# 02_Power.net
KiCad netlist of a schematic drawn in Altium Designer
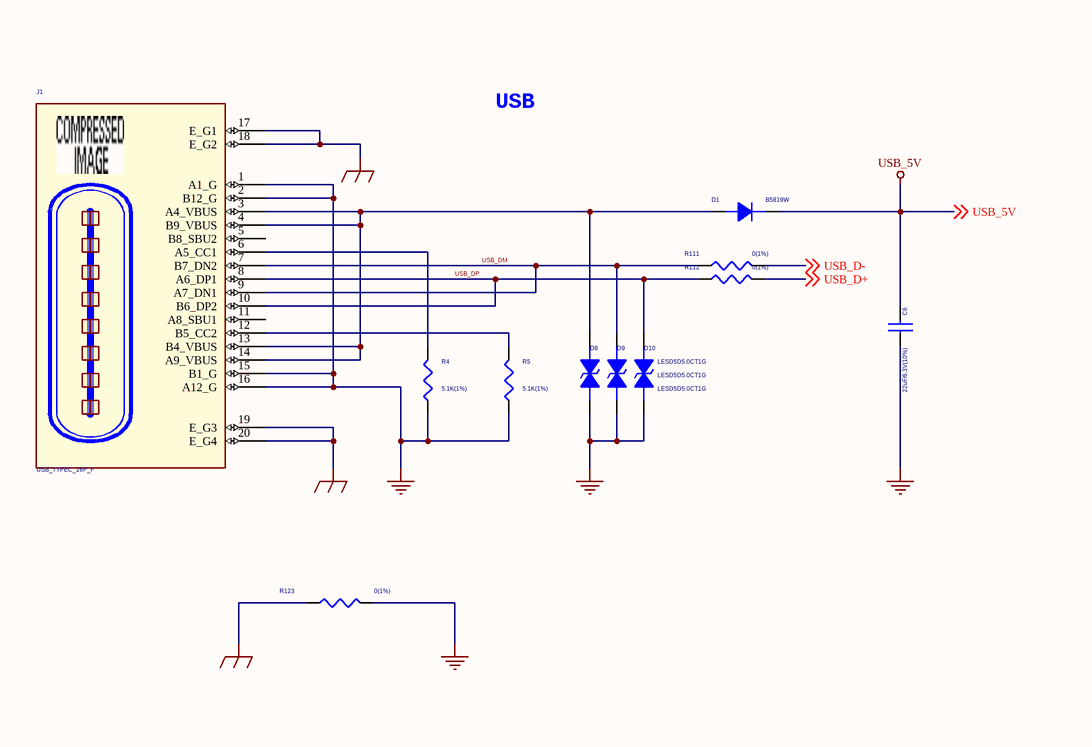
[diagram p0: 02_Power.SchDoc, left]
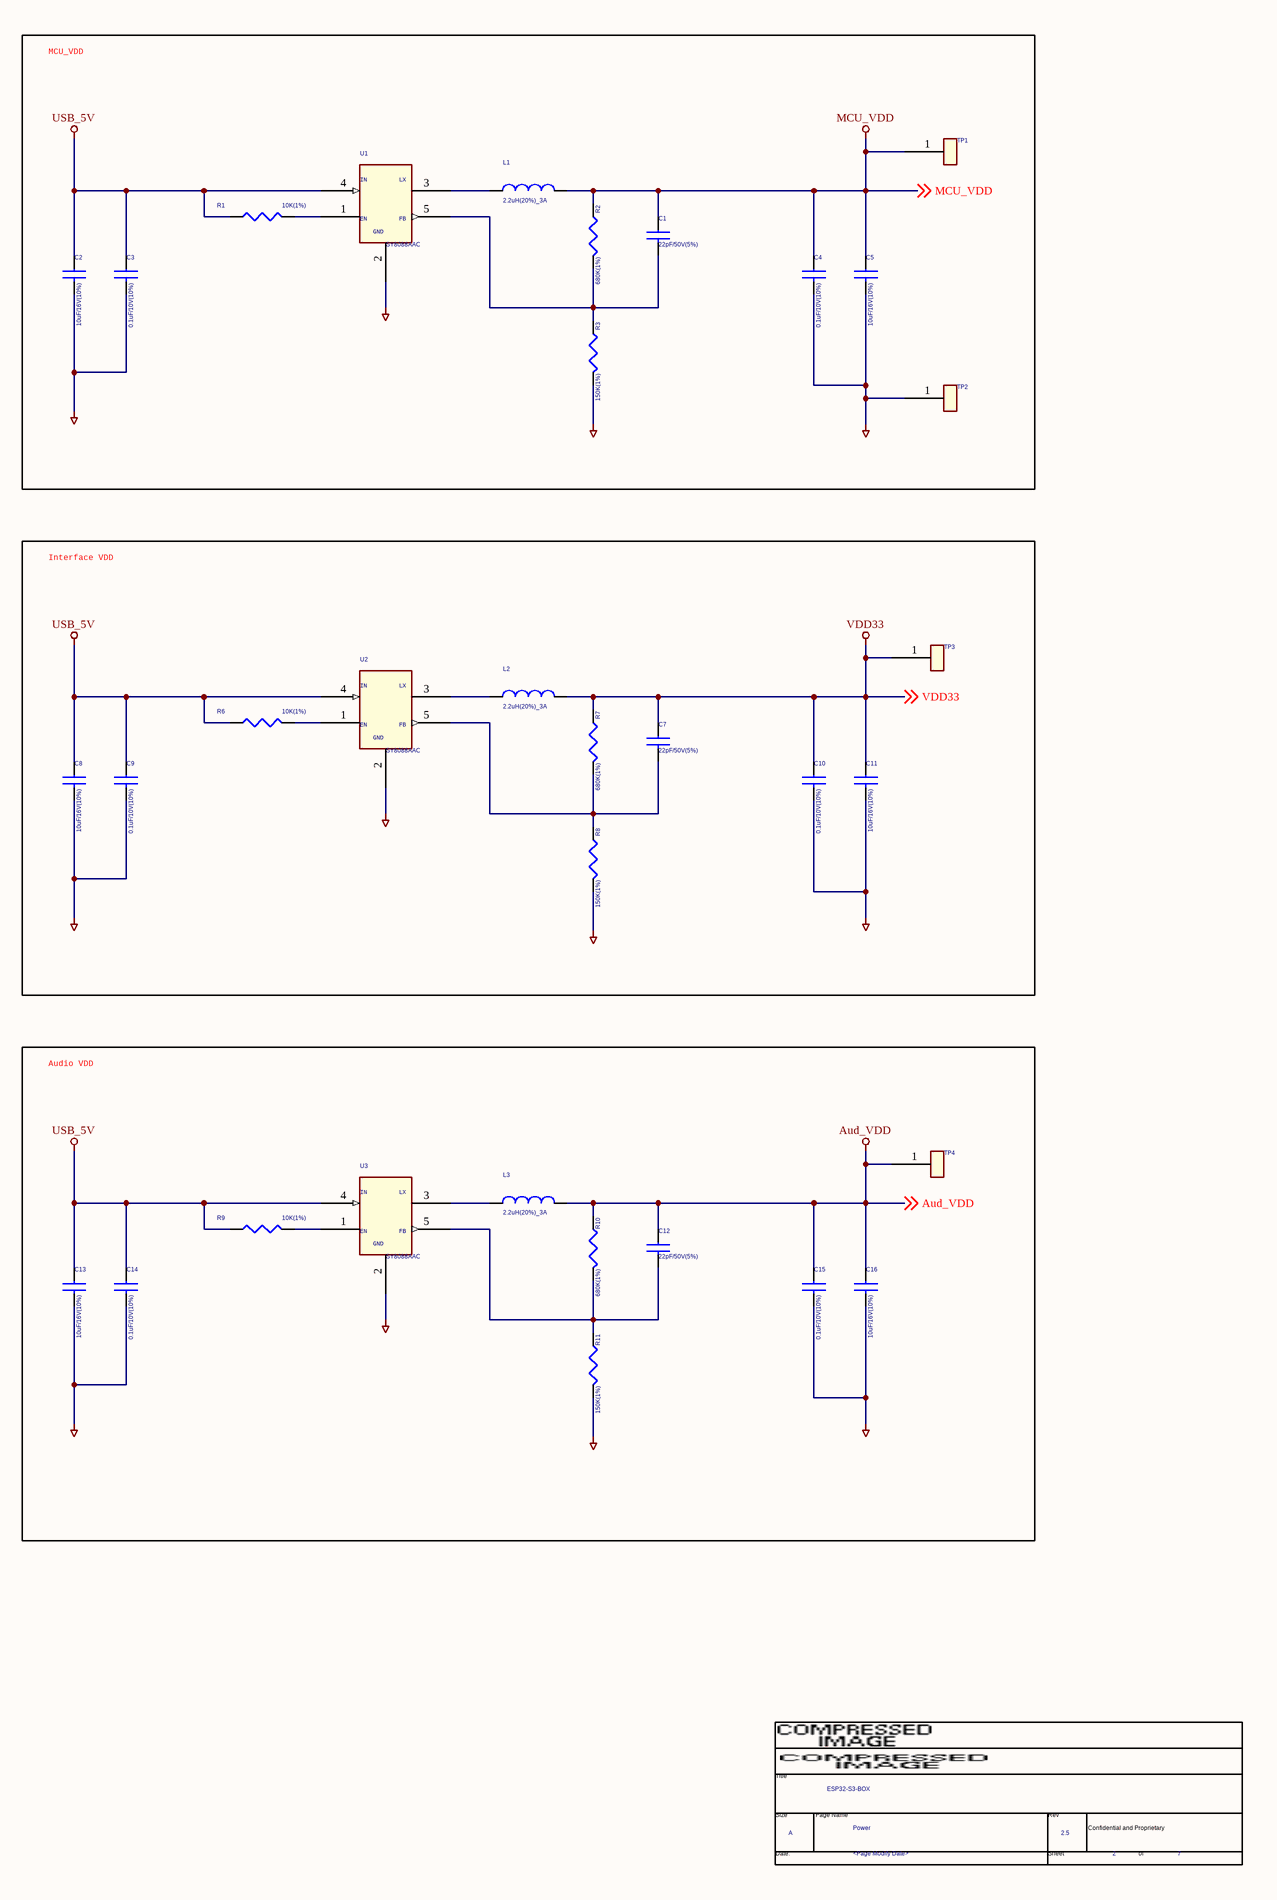
[diagram p1: 02_Power.SchDoc, right]

(export (version "E")
  (design (tool "Eeschema 10.0.6"))
  (components
    (comp (ref "*")
      (value "espTitleBlock3")
      (fields
        (field (name "PAGE MODIFY DATE") "<Page Modify Date>")
        (field (name "PAGE NAME") "Power")
        (field (name "TITLE") "ESP32-S3-BOX")
        (field (name "PAGE SIZE") "A")
        (field (name "PAGE NUMBER") "2")
        (field (name "PAGE COUNT") "7")
        (field (name "REVCODE") "2.5")
      )
      (libsource (lib "*") (part "espTitleBlock3"))
    )
    (comp (ref "C1")
      (value "22pF/50V(5%)")
      (footprint "C0402")
      (fields (field (name "PART NUMBER") "ES11041226520001"))
      (libsource (lib "*") (part "CAPACITOR"))
    )
    (comp (ref "C2")
      (value "10uF/16V(10%)")
      (footprint "C0603")
      (fields (field (name "PART NUMBER") "ES11067104600000"))
      (libsource (lib "*") (part "CAPACITOR"))
    )
    (comp (ref "C3")
      (value "0.1uF/10V(10%)")
      (footprint "C0402")
      (fields (field (name "PART NUMBER") "ES11045103620000"))
      (libsource (lib "*") (part "CAPACITOR"))
    )
    (comp (ref "C4")
      (value "0.1uF/10V(10%)")
      (footprint "C0402")
      (fields (field (name "PART NUMBER") "ES11045103620000"))
      (libsource (lib "*") (part "CAPACITOR"))
    )
    (comp (ref "C5")
      (value "10uF/16V(10%)")
      (footprint "C0603")
      (fields (field (name "PART NUMBER") "ES11067104600000"))
      (libsource (lib "*") (part "CAPACITOR"))
    )
    (comp (ref "C6")
      (value "22uF/6.3V(10%)")
      (footprint "C0603")
      (fields (field (name "PART NUMBER") "ES11067222600001"))
      (libsource (lib "*") (part "CAPACITOR"))
    )
    (comp (ref "C7")
      (value "22pF/50V(5%)")
      (footprint "C0402")
      (fields (field (name "PART NUMBER") "ES11041226520001"))
      (libsource (lib "*") (part "CAPACITOR"))
    )
    (comp (ref "C8")
      (value "10uF/16V(10%)")
      (footprint "C0603")
      (fields (field (name "PART NUMBER") "ES11067104600000"))
      (libsource (lib "*") (part "CAPACITOR"))
    )
    (comp (ref "C9")
      (value "0.1uF/10V(10%)")
      (footprint "C0402")
      (fields (field (name "PART NUMBER") "ES11045103620000"))
      (libsource (lib "*") (part "CAPACITOR"))
    )
    (comp (ref "C10")
      (value "0.1uF/10V(10%)")
      (footprint "C0402")
      (fields (field (name "PART NUMBER") "ES11045103620000"))
      (libsource (lib "*") (part "CAPACITOR"))
    )
    (comp (ref "C11")
      (value "10uF/16V(10%)")
      (footprint "C0603")
      (fields (field (name "PART NUMBER") "ES11067104600000"))
      (libsource (lib "*") (part "CAPACITOR"))
    )
    (comp (ref "C12")
      (value "22pF/50V(5%)")
      (footprint "C0402")
      (fields (field (name "PART NUMBER") "ES11041226520001"))
      (libsource (lib "*") (part "CAPACITOR"))
    )
    (comp (ref "C13")
      (value "10uF/16V(10%)")
      (footprint "C0603")
      (fields (field (name "PART NUMBER") "ES11067104600000"))
      (libsource (lib "*") (part "CAPACITOR"))
    )
    (comp (ref "C14")
      (value "0.1uF/10V(10%)")
      (footprint "C0402")
      (fields (field (name "PART NUMBER") "ES11045103620000"))
      (libsource (lib "*") (part "CAPACITOR"))
    )
    (comp (ref "C15")
      (value "0.1uF/10V(10%)")
      (footprint "C0402")
      (fields (field (name "PART NUMBER") "ES11045103620000"))
      (libsource (lib "*") (part "CAPACITOR"))
    )
    (comp (ref "C16")
      (value "10uF/16V(10%)")
      (footprint "C0603")
      (fields (field (name "PART NUMBER") "ES11067104600000"))
      (libsource (lib "*") (part "CAPACITOR"))
    )
    (comp (ref "D1")
      (value "B5819W")
      (footprint "SOD123")
      (fields (field (name "PART NUMBER") "ES31300150000000"))
      (libsource (lib "*") (part "DIODE_S"))
    )
    (comp (ref "D8")
      (value "LESD5D5.0CT1G")
      (footprint "SOD523")
      (fields (field (name "PART NUMBER") "ES31320020000000"))
      (libsource (lib "*") (part "DIODE_BI_DIR"))
    )
    (comp (ref "D9")
      (value "LESD5D5.0CT1G")
      (footprint "SOD523")
      (fields (field (name "PART NUMBER") "ES31320020000000"))
      (libsource (lib "*") (part "DIODE_BI_DIR"))
    )
    (comp (ref "D10")
      (value "LESD5D5.0CT1G")
      (footprint "SOD523")
      (fields (field (name "PART NUMBER") "ES31320020000000"))
      (libsource (lib "*") (part "DIODE_BI_DIR"))
    )
    (comp (ref "J1")
      (value "USB_TYPEC_16P_F")
      (footprint "USB_TYPEC_16P_F")
      (fields (field (name "PART NUMBER") "ES52220020000000"))
      (libsource (lib "*") (part "USB_TYPEC_16P_F"))
    )
    (comp (ref "L1")
      (value "2.2uH(20%)_3A")
      (footprint "L4040_SL")
      (libsource (lib "*") (part "INDUCTOR_Dup1"))
    )
    (comp (ref "L2")
      (value "2.2uH(20%)_3A")
      (footprint "L4040_SL")
      (libsource (lib "*") (part "INDUCTOR_Dup1"))
    )
    (comp (ref "L3")
      (value "2.2uH(20%)_3A")
      (footprint "L4040_SL")
      (libsource (lib "*") (part "INDUCTOR_Dup1"))
    )
    (comp (ref "R1")
      (value "10K(1%)")
      (footprint "R0402")
      (fields (field (name "PART NUMBER") "ES21044100000001"))
      (libsource (lib "*") (part "RESISTOR"))
    )
    (comp (ref "R2")
      (value "680K(1%)")
      (footprint "R0402")
      (fields (field (name "PART NUMBER") "ES21045680000001"))
      (libsource (lib "*") (part "RESISTOR"))
    )
    (comp (ref "R3")
      (value "150K(1%)")
      (footprint "R0402")
      (fields (field (name "PART NUMBER") "ES21045150000001"))
      (libsource (lib "*") (part "RESISTOR"))
    )
    (comp (ref "R4")
      (value "5.1K(1%)")
      (footprint "R0201")
      (fields (field (name "PART NUMBER") "ES21023510000001"))
      (libsource (lib "*") (part "RESISTOR"))
    )
    (comp (ref "R5")
      (value "5.1K(1%)")
      (footprint "R0201")
      (fields (field (name "PART NUMBER") "ES21023510000001"))
      (libsource (lib "*") (part "RESISTOR"))
    )
    (comp (ref "R6")
      (value "10K(1%)")
      (footprint "R0402")
      (fields (field (name "PART NUMBER") "ES21044100000001"))
      (libsource (lib "*") (part "RESISTOR"))
    )
    (comp (ref "R7")
      (value "680K(1%)")
      (footprint "R0402")
      (fields (field (name "PART NUMBER") "ES21045680000001"))
      (libsource (lib "*") (part "RESISTOR"))
    )
    (comp (ref "R8")
      (value "150K(1%)")
      (footprint "R0402")
      (fields (field (name "PART NUMBER") "ES21045150000001"))
      (libsource (lib "*") (part "RESISTOR"))
    )
    (comp (ref "R9")
      (value "10K(1%)")
      (footprint "R0402")
      (fields (field (name "PART NUMBER") "ES21044100000001"))
      (libsource (lib "*") (part "RESISTOR"))
    )
    (comp (ref "R10")
      (value "680K(1%)")
      (footprint "R0402")
      (fields (field (name "PART NUMBER") "ES21045680000001"))
      (libsource (lib "*") (part "RESISTOR"))
    )
    (comp (ref "R11")
      (value "150K(1%)")
      (footprint "R0402")
      (fields (field (name "PART NUMBER") "ES21045150000001"))
      (libsource (lib "*") (part "RESISTOR"))
    )
    (comp (ref "R111")
      (value "0(1%)")
      (footprint "R0201")
      (fields (field (name "PART NUMBER") "ES21020000000001"))
      (libsource (lib "*") (part "RESISTOR"))
    )
    (comp (ref "R112")
      (value "0(1%)")
      (footprint "R0201")
      (fields (field (name "PART NUMBER") "ES21020000000001"))
      (libsource (lib "*") (part "RESISTOR"))
    )
    (comp (ref "R123")
      (value "0(1%)")
      (footprint "R0603")
      (fields (field (name "PART NUMBER") "ES21060000000001"))
      (libsource (lib "*") (part "RESISTOR"))
    )
    (comp (ref "TP1") (value "TESTPOINT") (footprint "TPC_D40") (libsource (lib "*") (part "TESTPOINT")))
    (comp (ref "TP2") (value "TESTPOINT") (footprint "TPC_D40") (libsource (lib "*") (part "TESTPOINT")))
    (comp (ref "TP3") (value "TESTPOINT") (footprint "TPC_D40") (libsource (lib "*") (part "TESTPOINT")))
    (comp (ref "TP4") (value "TESTPOINT") (footprint "TPC_D40") (libsource (lib "*") (part "TESTPOINT")))
    (comp (ref "U1")
      (value "SY8088AAC")
      (footprint "SOT23-5")
      (fields (field (name "PART NUMBER") "ES41140401000000"))
      (libsource (lib "*") (part "SY808X"))
    )
    (comp (ref "U2")
      (value "SY8088AAC")
      (footprint "SOT23-5")
      (fields (field (name "PART NUMBER") "ES41140401000000"))
      (libsource (lib "*") (part "SY808X"))
    )
    (comp (ref "U3")
      (value "SY8088AAC")
      (footprint "SOT23-5")
      (fields (field (name "PART NUMBER") "ES41140401000000"))
      (libsource (lib "*") (part "SY808X"))
    )
  )
  (nets
    (net (code "1") (name "/USB_DM") (class "Default")
      (node (ref "D9") (pin "2") (pinfunction "2_2") (pintype "passive"))
      (node (ref "J1") (pin "7") (pinfunction "B7_DN2_7") (pintype "bidirectional"))
      (node (ref "J1") (pin "9") (pinfunction "A7_DN1_9") (pintype "bidirectional"))
      (node (ref "R111") (pin "1") (pinfunction "1_1") (pintype "passive"))
    )
    (net (code "2") (name "/USB_DP") (class "Default")
      (node (ref "D10") (pin "2") (pinfunction "2_2") (pintype "passive"))
      (node (ref "J1") (pin "10") (pinfunction "B6_DP2_10") (pintype "bidirectional"))
      (node (ref "J1") (pin "8") (pinfunction "A6_DP1_8") (pintype "bidirectional"))
      (node (ref "R112") (pin "1") (pinfunction "1_1") (pintype "passive"))
    )
    (net (code "3") (name "Aud_VDD") (class "Default")
      (node (ref "C12") (pin "1") (pinfunction "1_1") (pintype "passive"))
      (node (ref "C15") (pin "1") (pinfunction "1_1") (pintype "passive"))
      (node (ref "C16") (pin "1") (pinfunction "1_1") (pintype "passive"))
      (node (ref "L3") (pin "2") (pinfunction "2_2") (pintype "passive"))
      (node (ref "R10") (pin "1") (pinfunction "1_1") (pintype "passive"))
      (node (ref "TP4") (pin "1") (pinfunction "1_1") (pintype "passive"))
    )
    (net (code "4") (name "GND") (class "Default")
      (node (ref "C10") (pin "2") (pinfunction "2_2") (pintype "passive"))
      (node (ref "C11") (pin "2") (pinfunction "2_2") (pintype "passive"))
      (node (ref "C13") (pin "2") (pinfunction "2_2") (pintype "passive"))
      (node (ref "C14") (pin "2") (pinfunction "2_2") (pintype "passive"))
      (node (ref "C15") (pin "2") (pinfunction "2_2") (pintype "passive"))
      (node (ref "C16") (pin "2") (pinfunction "2_2") (pintype "passive"))
      (node (ref "C2") (pin "2") (pinfunction "2_2") (pintype "passive"))
      (node (ref "C3") (pin "2") (pinfunction "2_2") (pintype "passive"))
      (node (ref "C4") (pin "2") (pinfunction "2_2") (pintype "passive"))
      (node (ref "C5") (pin "2") (pinfunction "2_2") (pintype "passive"))
      (node (ref "C6") (pin "1") (pinfunction "1_1") (pintype "passive"))
      (node (ref "C8") (pin "2") (pinfunction "2_2") (pintype "passive"))
      (node (ref "C9") (pin "2") (pinfunction "2_2") (pintype "passive"))
      (node (ref "D10") (pin "1") (pinfunction "1_1") (pintype "passive"))
      (node (ref "D8") (pin "1") (pinfunction "1_1") (pintype "passive"))
      (node (ref "D9") (pin "1") (pinfunction "1_1") (pintype "passive"))
      (node (ref "J1") (pin "1") (pinfunction "A1_G_1") (pintype "bidirectional"))
      (node (ref "J1") (pin "15") (pinfunction "B1_G_15") (pintype "bidirectional"))
      (node (ref "J1") (pin "16") (pinfunction "A12_G_16") (pintype "bidirectional"))
      (node (ref "J1") (pin "2") (pinfunction "B12_G_2") (pintype "bidirectional"))
      (node (ref "R11") (pin "2") (pinfunction "2_2") (pintype "passive"))
      (node (ref "R123") (pin "2") (pinfunction "2_2") (pintype "passive"))
      (node (ref "R3") (pin "2") (pinfunction "2_2") (pintype "passive"))
      (node (ref "R4") (pin "1") (pinfunction "1_1") (pintype "passive"))
      (node (ref "R5") (pin "1") (pinfunction "1_1") (pintype "passive"))
      (node (ref "R8") (pin "2") (pinfunction "2_2") (pintype "passive"))
      (node (ref "TP2") (pin "1") (pinfunction "1_1") (pintype "passive"))
      (node (ref "U1") (pin "2") (pinfunction "GND_2") (pintype "power_in"))
      (node (ref "U2") (pin "2") (pinfunction "GND_2") (pintype "power_in"))
      (node (ref "U3") (pin "2") (pinfunction "GND_2") (pintype "power_in"))
    )
    (net (code "5") (name "GND_EARTH") (class "Default")
      (node (ref "J1") (pin "17") (pinfunction "E_G1_17") (pintype "bidirectional"))
      (node (ref "J1") (pin "18") (pinfunction "E_G2_18") (pintype "bidirectional"))
      (node (ref "J1") (pin "19") (pinfunction "E_G3_19") (pintype "bidirectional"))
      (node (ref "J1") (pin "20") (pinfunction "E_G4_20") (pintype "bidirectional"))
      (node (ref "R123") (pin "1") (pinfunction "1_1") (pintype "passive"))
    )
    (net (code "6") (name "MCU_VDD") (class "Default")
      (node (ref "C1") (pin "1") (pinfunction "1_1") (pintype "passive"))
      (node (ref "C4") (pin "1") (pinfunction "1_1") (pintype "passive"))
      (node (ref "C5") (pin "1") (pinfunction "1_1") (pintype "passive"))
      (node (ref "L1") (pin "2") (pinfunction "2_2") (pintype "passive"))
      (node (ref "R2") (pin "1") (pinfunction "1_1") (pintype "passive"))
      (node (ref "TP1") (pin "1") (pinfunction "1_1") (pintype "passive"))
    )
    (net (code "7") (name "Net-(D1-A)") (class "Default")
      (node (ref "D1") (pin "1") (pinfunction "A_1") (pintype "passive"))
      (node (ref "D8") (pin "2") (pinfunction "2_2") (pintype "passive"))
      (node (ref "J1") (pin "13") (pinfunction "B4_VBUS_13") (pintype "bidirectional"))
      (node (ref "J1") (pin "14") (pinfunction "A9_VBUS_14") (pintype "bidirectional"))
      (node (ref "J1") (pin "3") (pinfunction "A4_VBUS_3") (pintype "bidirectional"))
      (node (ref "J1") (pin "4") (pinfunction "B9_VBUS_4") (pintype "bidirectional"))
    )
    (net (code "8") (name "Net-(J1-A5_CC1)") (class "Default")
      (node (ref "J1") (pin "6") (pinfunction "A5_CC1_6") (pintype "bidirectional"))
      (node (ref "R4") (pin "2") (pinfunction "2_2") (pintype "passive"))
    )
    (net (code "9") (name "Net-(J1-B5_CC2)") (class "Default")
      (node (ref "J1") (pin "12") (pinfunction "B5_CC2_12") (pintype "bidirectional"))
      (node (ref "R5") (pin "2") (pinfunction "2_2") (pintype "passive"))
    )
    (net (code "10") (name "Net-(U1-EN)") (class "Default")
      (node (ref "R1") (pin "2") (pinfunction "2_2") (pintype "passive"))
      (node (ref "U1") (pin "1") (pinfunction "EN_1") (pintype "passive"))
    )
    (net (code "11") (name "Net-(U1-FB)") (class "Default")
      (node (ref "C1") (pin "2") (pinfunction "2_2") (pintype "passive"))
      (node (ref "R2") (pin "2") (pinfunction "2_2") (pintype "passive"))
      (node (ref "R3") (pin "1") (pinfunction "1_1") (pintype "passive"))
      (node (ref "U1") (pin "5") (pinfunction "FB_5") (pintype "output"))
    )
    (net (code "12") (name "Net-(U1-LX)") (class "Default")
      (node (ref "L1") (pin "1") (pinfunction "1_1") (pintype "passive"))
      (node (ref "U1") (pin "3") (pinfunction "LX_3") (pintype "passive"))
    )
    (net (code "13") (name "Net-(U2-EN)") (class "Default")
      (node (ref "R6") (pin "2") (pinfunction "2_2") (pintype "passive"))
      (node (ref "U2") (pin "1") (pinfunction "EN_1") (pintype "passive"))
    )
    (net (code "14") (name "Net-(U2-FB)") (class "Default")
      (node (ref "C7") (pin "2") (pinfunction "2_2") (pintype "passive"))
      (node (ref "R7") (pin "2") (pinfunction "2_2") (pintype "passive"))
      (node (ref "R8") (pin "1") (pinfunction "1_1") (pintype "passive"))
      (node (ref "U2") (pin "5") (pinfunction "FB_5") (pintype "output"))
    )
    (net (code "15") (name "Net-(U2-LX)") (class "Default")
      (node (ref "L2") (pin "1") (pinfunction "1_1") (pintype "passive"))
      (node (ref "U2") (pin "3") (pinfunction "LX_3") (pintype "passive"))
    )
    (net (code "16") (name "Net-(U3-EN)") (class "Default")
      (node (ref "R9") (pin "2") (pinfunction "2_2") (pintype "passive"))
      (node (ref "U3") (pin "1") (pinfunction "EN_1") (pintype "passive"))
    )
    (net (code "17") (name "Net-(U3-FB)") (class "Default")
      (node (ref "C12") (pin "2") (pinfunction "2_2") (pintype "passive"))
      (node (ref "R10") (pin "2") (pinfunction "2_2") (pintype "passive"))
      (node (ref "R11") (pin "1") (pinfunction "1_1") (pintype "passive"))
      (node (ref "U3") (pin "5") (pinfunction "FB_5") (pintype "output"))
    )
    (net (code "18") (name "Net-(U3-LX)") (class "Default")
      (node (ref "L3") (pin "1") (pinfunction "1_1") (pintype "passive"))
      (node (ref "U3") (pin "3") (pinfunction "LX_3") (pintype "passive"))
    )
    (net (code "19") (name "USB_5V") (class "Default")
      (node (ref "C13") (pin "1") (pinfunction "1_1") (pintype "passive"))
      (node (ref "C14") (pin "1") (pinfunction "1_1") (pintype "passive"))
      (node (ref "C2") (pin "1") (pinfunction "1_1") (pintype "passive"))
      (node (ref "C3") (pin "1") (pinfunction "1_1") (pintype "passive"))
      (node (ref "C6") (pin "2") (pinfunction "2_2") (pintype "passive"))
      (node (ref "C8") (pin "1") (pinfunction "1_1") (pintype "passive"))
      (node (ref "C9") (pin "1") (pinfunction "1_1") (pintype "passive"))
      (node (ref "D1") (pin "2") (pinfunction "K_2") (pintype "passive"))
      (node (ref "R1") (pin "1") (pinfunction "1_1") (pintype "passive"))
      (node (ref "R6") (pin "1") (pinfunction "1_1") (pintype "passive"))
      (node (ref "R9") (pin "1") (pinfunction "1_1") (pintype "passive"))
      (node (ref "U1") (pin "4") (pinfunction "IN_4") (pintype "input"))
      (node (ref "U2") (pin "4") (pinfunction "IN_4") (pintype "input"))
      (node (ref "U3") (pin "4") (pinfunction "IN_4") (pintype "input"))
    )
    (net (code "20") (name "USB_D+") (class "Default")
      (node (ref "R112") (pin "2") (pinfunction "2_2") (pintype "passive"))
    )
    (net (code "21") (name "USB_D-") (class "Default")
      (node (ref "R111") (pin "2") (pinfunction "2_2") (pintype "passive"))
    )
    (net (code "22") (name "VDD33") (class "Default")
      (node (ref "C10") (pin "1") (pinfunction "1_1") (pintype "passive"))
      (node (ref "C11") (pin "1") (pinfunction "1_1") (pintype "passive"))
      (node (ref "C7") (pin "1") (pinfunction "1_1") (pintype "passive"))
      (node (ref "L2") (pin "2") (pinfunction "2_2") (pintype "passive"))
      (node (ref "R7") (pin "1") (pinfunction "1_1") (pintype "passive"))
      (node (ref "TP3") (pin "1") (pinfunction "1_1") (pintype "passive"))
    )
    (net (code "23") (name "unconnected-(J1-A8_SBU1-Pad11)") (class "Default")
      (node (ref "J1") (pin "11") (pinfunction "A8_SBU1_11") (pintype "bidirectional"))
    )
    (net (code "24") (name "unconnected-(J1-B8_SBU2-Pad5)") (class "Default")
      (node (ref "J1") (pin "5") (pinfunction "B8_SBU2_5") (pintype "bidirectional"))
    )
  )
)
